# Adafruit_128x32_Pi_OLED.net
KiCad netlist of a schematic drawn in EAGLE
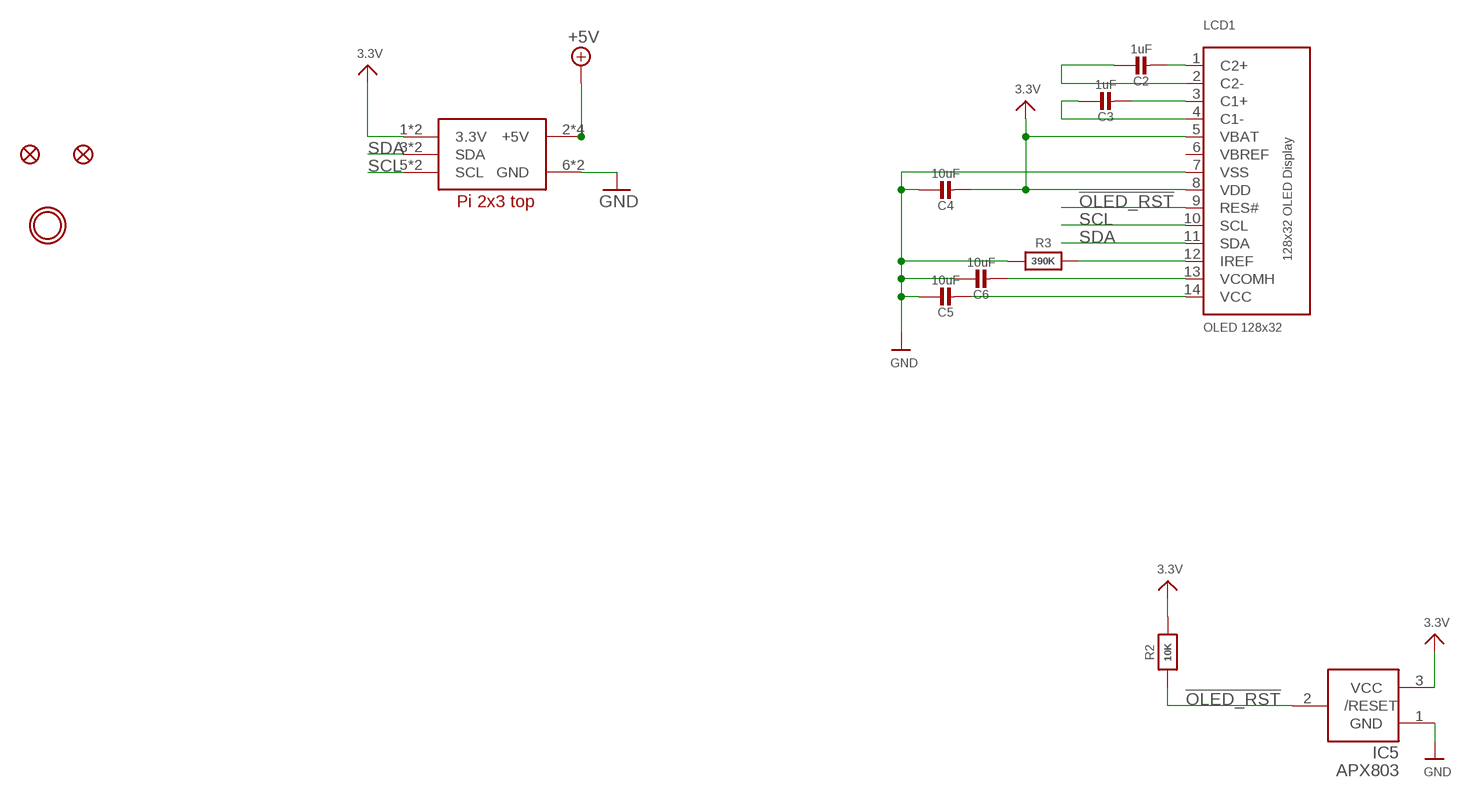
[diagram p0: schematic, sheet 1]

(export (version "E")
  (design (tool "Eeschema 10.0.6"))
  (components
    (comp (ref "C2")
      (value "1uF")
      (footprint "eagle-import:0805-NO")
      (libsource (lib "eagle-import") (part "CAP_CERAMIC0805-NOOUTLINE"))
    )
    (comp (ref "C3")
      (value "1uF")
      (footprint "eagle-import:0805-NO")
      (libsource (lib "eagle-import") (part "CAP_CERAMIC0805-NOOUTLINE"))
    )
    (comp (ref "C4")
      (value "10uF")
      (footprint "eagle-import:0805-NO")
      (libsource (lib "eagle-import") (part "CAP_CERAMIC0805-NOOUTLINE"))
    )
    (comp (ref "C5")
      (value "10uF")
      (footprint "eagle-import:0805-NO")
      (libsource (lib "eagle-import") (part "CAP_CERAMIC0805-NOOUTLINE"))
    )
    (comp (ref "C6")
      (value "10uF")
      (footprint "eagle-import:0805-NO")
      (libsource (lib "eagle-import") (part "CAP_CERAMIC0805-NOOUTLINE"))
    )
    (comp (ref "FID3")
      (value "FIDUCIAL_1MM")
      (footprint "eagle-import:FIDUCIAL_1MM")
      (libsource (lib "eagle-import") (part "FIDUCIAL_1MM"))
    )
    (comp (ref "FID4")
      (value "FIDUCIAL_1MM")
      (footprint "eagle-import:FIDUCIAL_1MM")
      (libsource (lib "eagle-import") (part "FIDUCIAL_1MM"))
    )
    (comp (ref "IC5")
      (value "APX803")
      (footprint "eagle-import:SOT23")
      (libsource (lib "eagle-import") (part "AXP083-SAG"))
    )
    (comp (ref "LCD1")
      (value "OLED 128x32")
      (footprint "eagle-import:UG-2832HSWEG02_WRAPUNDER")
      (libsource (lib "eagle-import") (part "DISP_OLED_UG-2832HSWEG02"))
    )
    (comp (ref "R2")
      (value "10K")
      (footprint "eagle-import:0805-NO")
      (libsource (lib "eagle-import") (part "RESISTOR0805_NOOUTLINE"))
    )
    (comp (ref "R3")
      (value "390K")
      (footprint "eagle-import:0805-NO")
      (libsource (lib "eagle-import") (part "RESISTOR0805_NOOUTLINE"))
    )
    (comp (ref "RPI1")
      (value "RASPBERRYPI_2X3")
      (footprint "eagle-import:RASPBERRYPI_2X3_THMSMT")
      (libsource (lib "eagle-import") (part "RASPBERRYPI_2X3"))
    )
    (comp (ref "U$4")
      (value "MOUNTINGHOLE3.0THIN")
      (footprint "eagle-import:MOUNTINGHOLE_3.0_PLATEDTHIN")
      (libsource (lib "eagle-import") (part "MOUNTINGHOLE3.0THIN"))
    )
  )
  (nets
    (net (code "1") (name "+5V") (class "Default")
      (node (ref "RPI1") (pin "2") (pinfunction "+5V_2") (pintype "bidirectional"))
      (node (ref "RPI1") (pin "2'") (pinfunction "+5V_2'") (pintype "bidirectional"))
      (node (ref "RPI1") (pin "4") (pinfunction "+5V_4") (pintype "bidirectional"))
      (node (ref "RPI1") (pin "4'") (pinfunction "+5V_4'") (pintype "bidirectional"))
    )
    (net (code "2") (name "/SCL") (class "Default")
      (node (ref "LCD1") (pin "10") (pinfunction "SCL_10") (pintype "bidirectional"))
      (node (ref "RPI1") (pin "5") (pinfunction "SCL_5") (pintype "bidirectional"))
      (node (ref "RPI1") (pin "5'") (pinfunction "SCL_5'") (pintype "bidirectional"))
    )
    (net (code "3") (name "/SDA") (class "Default")
      (node (ref "LCD1") (pin "11") (pinfunction "SDA_11") (pintype "bidirectional"))
      (node (ref "RPI1") (pin "3") (pinfunction "SDA_3") (pintype "bidirectional"))
      (node (ref "RPI1") (pin "3'") (pinfunction "SDA_3'") (pintype "bidirectional"))
    )
    (net (code "4") (name "/VBREF") (class "Default")
      (node (ref "LCD1") (pin "6") (pinfunction "VBREF_6") (pintype "power_in"))
    )
    (net (code "5") (name "/~{OLED_RST}") (class "Default")
      (node (ref "IC5") (pin "2") (pinfunction "/RESET_2") (pintype "output"))
      (node (ref "LCD1") (pin "9") (pinfunction "RES#_9") (pintype "bidirectional"))
      (node (ref "R2") (pin "1") (pinfunction "1_1") (pintype "passive"))
    )
    (net (code "6") (name "3.3V") (class "Default")
      (node (ref "C4") (pin "2") (pinfunction "2_2") (pintype "passive"))
      (node (ref "IC5") (pin "3") (pinfunction "VCC_3") (pintype "power_in"))
      (node (ref "LCD1") (pin "5") (pinfunction "VBAT_5") (pintype "power_in"))
      (node (ref "LCD1") (pin "8") (pinfunction "VDD_8") (pintype "power_in"))
      (node (ref "R2") (pin "2") (pinfunction "2_2") (pintype "passive"))
      (node (ref "RPI1") (pin "1") (pinfunction "3.3V_1") (pintype "bidirectional"))
      (node (ref "RPI1") (pin "1'") (pinfunction "3.3V_1'") (pintype "bidirectional"))
    )
    (net (code "7") (name "GND") (class "Default")
      (node (ref "C4") (pin "1") (pinfunction "1_1") (pintype "passive"))
      (node (ref "C5") (pin "1") (pinfunction "1_1") (pintype "passive"))
      (node (ref "C6") (pin "1") (pinfunction "1_1") (pintype "passive"))
      (node (ref "IC5") (pin "1") (pinfunction "GND_1") (pintype "power_in"))
      (node (ref "LCD1") (pin "7") (pinfunction "VSS_7") (pintype "power_in"))
      (node (ref "R3") (pin "1") (pinfunction "1_1") (pintype "passive"))
      (node (ref "RPI1") (pin "6") (pinfunction "GND_6") (pintype "bidirectional"))
      (node (ref "RPI1") (pin "6'") (pinfunction "GND_6'") (pintype "bidirectional"))
    )
    (net (code "8") (name "Net-(LCD1-C1+)") (class "Default")
      (node (ref "C3") (pin "2") (pinfunction "2_2") (pintype "passive"))
      (node (ref "LCD1") (pin "3") (pinfunction "C1+_3") (pintype "bidirectional"))
    )
    (net (code "9") (name "Net-(LCD1-C1-)") (class "Default")
      (node (ref "C3") (pin "1") (pinfunction "1_1") (pintype "passive"))
      (node (ref "LCD1") (pin "4") (pinfunction "C1-_4") (pintype "bidirectional"))
    )
    (net (code "10") (name "Net-(LCD1-C2+)") (class "Default")
      (node (ref "C2") (pin "2") (pinfunction "2_2") (pintype "passive"))
      (node (ref "LCD1") (pin "1") (pinfunction "C2+_1") (pintype "bidirectional"))
    )
    (net (code "11") (name "Net-(LCD1-C2-)") (class "Default")
      (node (ref "C2") (pin "1") (pinfunction "1_1") (pintype "passive"))
      (node (ref "LCD1") (pin "2") (pinfunction "C2-_2") (pintype "bidirectional"))
    )
    (net (code "12") (name "Net-(LCD1-IREF)") (class "Default")
      (node (ref "LCD1") (pin "12") (pinfunction "IREF_12") (pintype "bidirectional"))
      (node (ref "R3") (pin "2") (pinfunction "2_2") (pintype "passive"))
    )
    (net (code "13") (name "Net-(LCD1-VCC)") (class "Default")
      (node (ref "C5") (pin "2") (pinfunction "2_2") (pintype "passive"))
      (node (ref "LCD1") (pin "14") (pinfunction "VCC_14") (pintype "power_in"))
    )
    (net (code "14") (name "Net-(LCD1-VCOMH)") (class "Default")
      (node (ref "C6") (pin "2") (pinfunction "2_2") (pintype "passive"))
      (node (ref "LCD1") (pin "13") (pinfunction "VCOMH_13") (pintype "power_in"))
    )
  )
)
